# Ngu-nghiep.net
KiCad netlist of a schematic drawn in Altium Designer
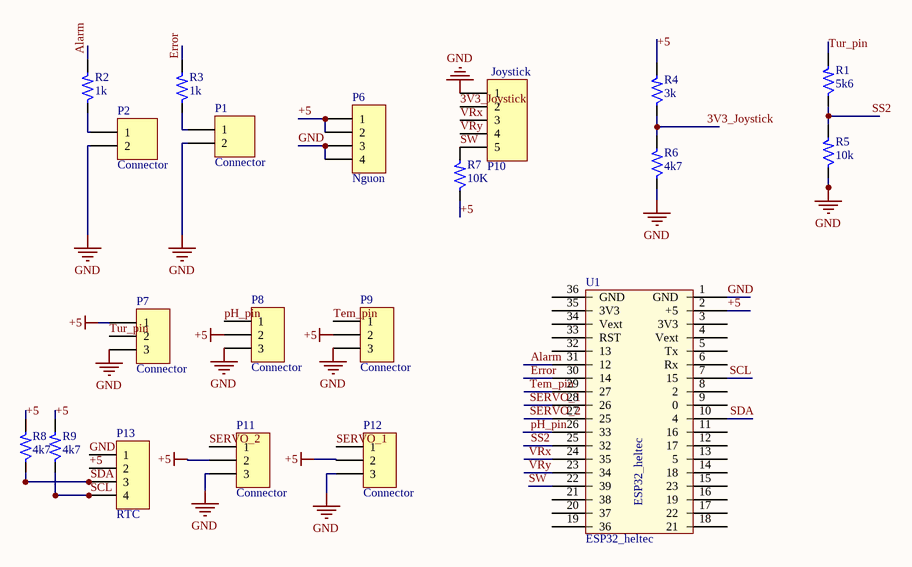
[diagram p0: Ngu-nghiep.schdoc]

(export (version "E")
  (design (tool "Eeschema 10.0.6"))
  (components
    (comp (ref "P1")
      (value "Connector")
      (footprint "MinhTien_PCBLib:JST-XH_B2B-XH-A")
      (libsource (lib "MinhTien_SCHLib") (part "Connector_2pin"))
    )
    (comp (ref "P2")
      (value "Connector")
      (footprint "MinhTien_PCBLib:JST-XH_B2B-XH-A")
      (libsource (lib "MinhTien_SCHLib") (part "Connector_2pin"))
    )
    (comp (ref "P6")
      (value "Nguon")
      (footprint "MinhTien_PCBLib:JST-XH_B4B-XH-A")
      (libsource (lib "MinhTien_SCHLib") (part "Connector_4pin"))
    )
    (comp (ref "P7")
      (value "Connector")
      (footprint "MinhTien_PCBLib:JST-XH_B3B-XH-A")
      (libsource (lib "MinhTien_SCHLib") (part "Connector_3pin"))
    )
    (comp (ref "P8")
      (value "Connector")
      (footprint "MinhTien_PCBLib:JST-XH_B3B-XH-A")
      (libsource (lib "MinhTien_SCHLib") (part "Connector_3pin"))
    )
    (comp (ref "P9")
      (value "Connector")
      (footprint "MinhTien_PCBLib:JST-XH_B3B-XH-A")
      (libsource (lib "MinhTien_SCHLib") (part "Connector_3pin"))
    )
    (comp (ref "P10")
      (value "Joystick")
      (footprint "MinhTien_PCBLib:JST-XH_B5B-XH-A")
      (libsource (lib "MinhTien_SCHLib") (part "Connector_5pin"))
    )
    (comp (ref "P11")
      (value "Connector")
      (footprint "MinhTien_PCBLib:JST-XH_B3B-XH-A")
      (libsource (lib "MinhTien_SCHLib") (part "Connector_3pin"))
    )
    (comp (ref "P12")
      (value "Connector")
      (footprint "MinhTien_PCBLib:JST-XH_B3B-XH-A")
      (libsource (lib "MinhTien_SCHLib") (part "Connector_3pin"))
    )
    (comp (ref "P13")
      (value "RTC")
      (footprint "MinhTien_PCBLib:JST-XH_B4B-XH-A")
      (libsource (lib "MinhTien_SCHLib") (part "Connector_4pin"))
    )
    (comp (ref "R1")
      (value "5k6")
      (footprint "R1/8W")
      (description "Resistor 1/4W")
      (libsource (lib "My Library") (part "R"))
    )
    (comp (ref "R2")
      (value "1k")
      (footprint "R1/8W")
      (description "Resistor 1/4W")
      (libsource (lib "My Library") (part "R"))
    )
    (comp (ref "R3")
      (value "1k")
      (footprint "R1/8W")
      (description "Resistor 1/4W")
      (libsource (lib "My Library") (part "R"))
    )
    (comp (ref "R4")
      (value "3k")
      (footprint "R1/8W")
      (description "Resistor 1/4W")
      (libsource (lib "My Library") (part "R"))
    )
    (comp (ref "R5")
      (value "10k")
      (footprint "R1/8W")
      (description "Resistor 1/4W")
      (libsource (lib "My Library") (part "R"))
    )
    (comp (ref "R6")
      (value "4k7")
      (footprint "R1/8W")
      (description "Resistor 1/4W")
      (libsource (lib "My Library") (part "R"))
    )
    (comp (ref "R7")
      (value "10K")
      (footprint "R1/8W")
      (description "Resistor 1/4W")
      (libsource (lib "My Library") (part "R"))
    )
    (comp (ref "R8")
      (value "4k7")
      (footprint "R1/8W")
      (description "Resistor 1/4W")
      (libsource (lib "My Library") (part "R"))
    )
    (comp (ref "R9")
      (value "4k7")
      (footprint "R1/8W")
      (description "Resistor 1/4W")
      (libsource (lib "My Library") (part "R"))
    )
    (comp (ref "U1")
      (value "ESP32_heltec")
      (footprint "ESP32_WFK_Heltec")
      (description "ESP32 IOT kit")
      (libsource (lib "MinhTien_SCHLib") (part "ESP32_heltec"))
    )
  )
  (nets
    (net (code "1") (name "+5") (class "Default")
      (node (ref "P11") (pin "2") (pinfunction "2_2") (pintype "passive"))
      (node (ref "P12") (pin "2") (pinfunction "2_2") (pintype "passive"))
      (node (ref "P13") (pin "2") (pinfunction "2_2") (pintype "passive"))
      (node (ref "P6") (pin "1") (pinfunction "1_1") (pintype "passive"))
      (node (ref "P6") (pin "2") (pinfunction "2_2") (pintype "passive"))
      (node (ref "P7") (pin "1") (pinfunction "1_1") (pintype "passive"))
      (node (ref "P8") (pin "2") (pinfunction "2_2") (pintype "passive"))
      (node (ref "P9") (pin "2") (pinfunction "2_2") (pintype "passive"))
      (node (ref "R4") (pin "2") (pinfunction "2_2") (pintype "passive"))
      (node (ref "R7") (pin "1") (pinfunction "1_1") (pintype "passive"))
      (node (ref "R8") (pin "2") (pinfunction "2_2") (pintype "passive"))
      (node (ref "R9") (pin "2") (pinfunction "2_2") (pintype "passive"))
      (node (ref "U1") (pin "2") (pinfunction "+5_2") (pintype "passive"))
    )
    (net (code "2") (name "/3V3_Joystick") (class "Default")
      (node (ref "P10") (pin "2") (pinfunction "2_2") (pintype "passive"))
      (node (ref "R4") (pin "1") (pinfunction "1_1") (pintype "passive"))
      (node (ref "R6") (pin "2") (pinfunction "2_2") (pintype "passive"))
    )
    (net (code "3") (name "/Alarm") (class "Default")
      (node (ref "R2") (pin "2") (pinfunction "2_2") (pintype "passive"))
      (node (ref "U1") (pin "31") (pinfunction "12_31") (pintype "passive"))
    )
    (net (code "4") (name "/Error") (class "Default")
      (node (ref "R3") (pin "2") (pinfunction "2_2") (pintype "passive"))
      (node (ref "U1") (pin "30") (pinfunction "14_30") (pintype "passive"))
    )
    (net (code "5") (name "/SCL") (class "Default")
      (node (ref "P13") (pin "4") (pinfunction "4_4") (pintype "passive"))
      (node (ref "R9") (pin "1") (pinfunction "1_1") (pintype "passive"))
      (node (ref "U1") (pin "7") (pinfunction "15_7") (pintype "passive"))
    )
    (net (code "6") (name "/SDA") (class "Default")
      (node (ref "P13") (pin "3") (pinfunction "3_3") (pintype "passive"))
      (node (ref "R8") (pin "1") (pinfunction "1_1") (pintype "passive"))
      (node (ref "U1") (pin "10") (pinfunction "4_10") (pintype "passive"))
    )
    (net (code "7") (name "/SERVO_1") (class "Default")
      (node (ref "P12") (pin "1") (pinfunction "1_1") (pintype "passive"))
      (node (ref "U1") (pin "28") (pinfunction "26_28") (pintype "passive"))
    )
    (net (code "8") (name "/SERVO_2") (class "Default")
      (node (ref "P11") (pin "1") (pinfunction "1_1") (pintype "passive"))
      (node (ref "U1") (pin "27") (pinfunction "25_27") (pintype "passive"))
    )
    (net (code "9") (name "/SS2") (class "Default")
      (node (ref "R1") (pin "1") (pinfunction "1_1") (pintype "passive"))
      (node (ref "R5") (pin "2") (pinfunction "2_2") (pintype "passive"))
      (node (ref "U1") (pin "25") (pinfunction "32_25") (pintype "passive"))
    )
    (net (code "10") (name "/SW") (class "Default")
      (node (ref "P10") (pin "5") (pinfunction "5_5") (pintype "passive"))
      (node (ref "R7") (pin "2") (pinfunction "2_2") (pintype "passive"))
      (node (ref "U1") (pin "22") (pinfunction "39_22") (pintype "passive"))
    )
    (net (code "11") (name "/Tem_pin") (class "Default")
      (node (ref "P9") (pin "1") (pinfunction "1_1") (pintype "passive"))
      (node (ref "U1") (pin "29") (pinfunction "27_29") (pintype "passive"))
    )
    (net (code "12") (name "/Tur_pin") (class "Default")
      (node (ref "P7") (pin "2") (pinfunction "2_2") (pintype "passive"))
      (node (ref "R1") (pin "2") (pinfunction "2_2") (pintype "passive"))
    )
    (net (code "13") (name "/VRx") (class "Default")
      (node (ref "P10") (pin "3") (pinfunction "3_3") (pintype "passive"))
      (node (ref "U1") (pin "24") (pinfunction "35_24") (pintype "passive"))
    )
    (net (code "14") (name "/VRy") (class "Default")
      (node (ref "P10") (pin "4") (pinfunction "4_4") (pintype "passive"))
      (node (ref "U1") (pin "23") (pinfunction "34_23") (pintype "passive"))
    )
    (net (code "15") (name "/pH_pin") (class "Default")
      (node (ref "P8") (pin "1") (pinfunction "1_1") (pintype "passive"))
      (node (ref "U1") (pin "26") (pinfunction "33_26") (pintype "passive"))
    )
    (net (code "16") (name "GND") (class "Default")
      (node (ref "P1") (pin "2") (pinfunction "2_2") (pintype "passive"))
      (node (ref "P10") (pin "1") (pinfunction "1_1") (pintype "passive"))
      (node (ref "P11") (pin "3") (pinfunction "3_3") (pintype "passive"))
      (node (ref "P12") (pin "3") (pinfunction "3_3") (pintype "passive"))
      (node (ref "P13") (pin "1") (pinfunction "1_1") (pintype "passive"))
      (node (ref "P2") (pin "2") (pinfunction "2_2") (pintype "passive"))
      (node (ref "P6") (pin "3") (pinfunction "3_3") (pintype "passive"))
      (node (ref "P6") (pin "4") (pinfunction "4_4") (pintype "passive"))
      (node (ref "P7") (pin "3") (pinfunction "3_3") (pintype "passive"))
      (node (ref "P8") (pin "3") (pinfunction "3_3") (pintype "passive"))
      (node (ref "P9") (pin "3") (pinfunction "3_3") (pintype "passive"))
      (node (ref "R5") (pin "1") (pinfunction "1_1") (pintype "passive"))
      (node (ref "R6") (pin "1") (pinfunction "1_1") (pintype "passive"))
      (node (ref "U1") (pin "1") (pinfunction "GND_1") (pintype "passive"))
    )
    (net (code "17") (name "Net-(P1-Pad1)") (class "Default")
      (node (ref "P1") (pin "1") (pinfunction "1_1") (pintype "passive"))
      (node (ref "R3") (pin "1") (pinfunction "1_1") (pintype "passive"))
    )
    (net (code "18") (name "Net-(P2-Pad1)") (class "Default")
      (node (ref "P2") (pin "1") (pinfunction "1_1") (pintype "passive"))
      (node (ref "R2") (pin "1") (pinfunction "1_1") (pintype "passive"))
    )
    (net (code "19") (name "unconnected-(U1-0-Pad9)") (class "Default")
      (node (ref "U1") (pin "9") (pinfunction "0_9") (pintype "passive"))
    )
    (net (code "20") (name "unconnected-(U1-2-Pad8)") (class "Default")
      (node (ref "U1") (pin "8") (pinfunction "2_8") (pintype "passive"))
    )
    (net (code "21") (name "unconnected-(U1-3V3-Pad3)") (class "Default")
      (node (ref "U1") (pin "3") (pinfunction "3V3_3") (pintype "passive"))
    )
    (net (code "22") (name "unconnected-(U1-3V3-Pad35)") (class "Default")
      (node (ref "U1") (pin "35") (pinfunction "3V3_35") (pintype "passive"))
    )
    (net (code "23") (name "unconnected-(U1-5-Pad13)") (class "Default")
      (node (ref "U1") (pin "13") (pinfunction "5_13") (pintype "passive"))
    )
    (net (code "24") (name "unconnected-(U1-13-Pad32)") (class "Default")
      (node (ref "U1") (pin "32") (pinfunction "13_32") (pintype "passive"))
    )
    (net (code "25") (name "unconnected-(U1-16-Pad11)") (class "Default")
      (node (ref "U1") (pin "11") (pinfunction "16_11") (pintype "passive"))
    )
    (net (code "26") (name "unconnected-(U1-17-Pad12)") (class "Default")
      (node (ref "U1") (pin "12") (pinfunction "17_12") (pintype "passive"))
    )
    (net (code "27") (name "unconnected-(U1-18-Pad14)") (class "Default")
      (node (ref "U1") (pin "14") (pinfunction "18_14") (pintype "passive"))
    )
    (net (code "28") (name "unconnected-(U1-19-Pad16)") (class "Default")
      (node (ref "U1") (pin "16") (pinfunction "19_16") (pintype "passive"))
    )
    (net (code "29") (name "unconnected-(U1-21-Pad18)") (class "Default")
      (node (ref "U1") (pin "18") (pinfunction "21_18") (pintype "passive"))
    )
    (net (code "30") (name "unconnected-(U1-22-Pad17)") (class "Default")
      (node (ref "U1") (pin "17") (pinfunction "22_17") (pintype "passive"))
    )
    (net (code "31") (name "unconnected-(U1-23-Pad15)") (class "Default")
      (node (ref "U1") (pin "15") (pinfunction "23_15") (pintype "passive"))
    )
    (net (code "32") (name "unconnected-(U1-36-Pad19)") (class "Default")
      (node (ref "U1") (pin "19") (pinfunction "36_19") (pintype "passive"))
    )
    (net (code "33") (name "unconnected-(U1-37-Pad20)") (class "Default")
      (node (ref "U1") (pin "20") (pinfunction "37_20") (pintype "passive"))
    )
    (net (code "34") (name "unconnected-(U1-38-Pad21)") (class "Default")
      (node (ref "U1") (pin "21") (pinfunction "38_21") (pintype "passive"))
    )
    (net (code "35") (name "unconnected-(U1-GND-Pad36)") (class "Default")
      (node (ref "U1") (pin "36") (pinfunction "GND_36") (pintype "passive"))
    )
    (net (code "36") (name "unconnected-(U1-RST-Pad33)") (class "Default")
      (node (ref "U1") (pin "33") (pinfunction "RST_33") (pintype "passive"))
    )
    (net (code "37") (name "unconnected-(U1-Rx-Pad6)") (class "Default")
      (node (ref "U1") (pin "6") (pinfunction "Rx_6") (pintype "passive"))
    )
    (net (code "38") (name "unconnected-(U1-Tx-Pad5)") (class "Default")
      (node (ref "U1") (pin "5") (pinfunction "Tx_5") (pintype "passive"))
    )
    (net (code "39") (name "unconnected-(U1-Vext-Pad4)") (class "Default")
      (node (ref "U1") (pin "4") (pinfunction "Vext_4") (pintype "passive"))
    )
    (net (code "40") (name "unconnected-(U1-Vext-Pad34)") (class "Default")
      (node (ref "U1") (pin "34") (pinfunction "Vext_34") (pintype "passive"))
    )
  )
)
